# M168A.net
KiCad netlist of a schematic drawn in EAGLE
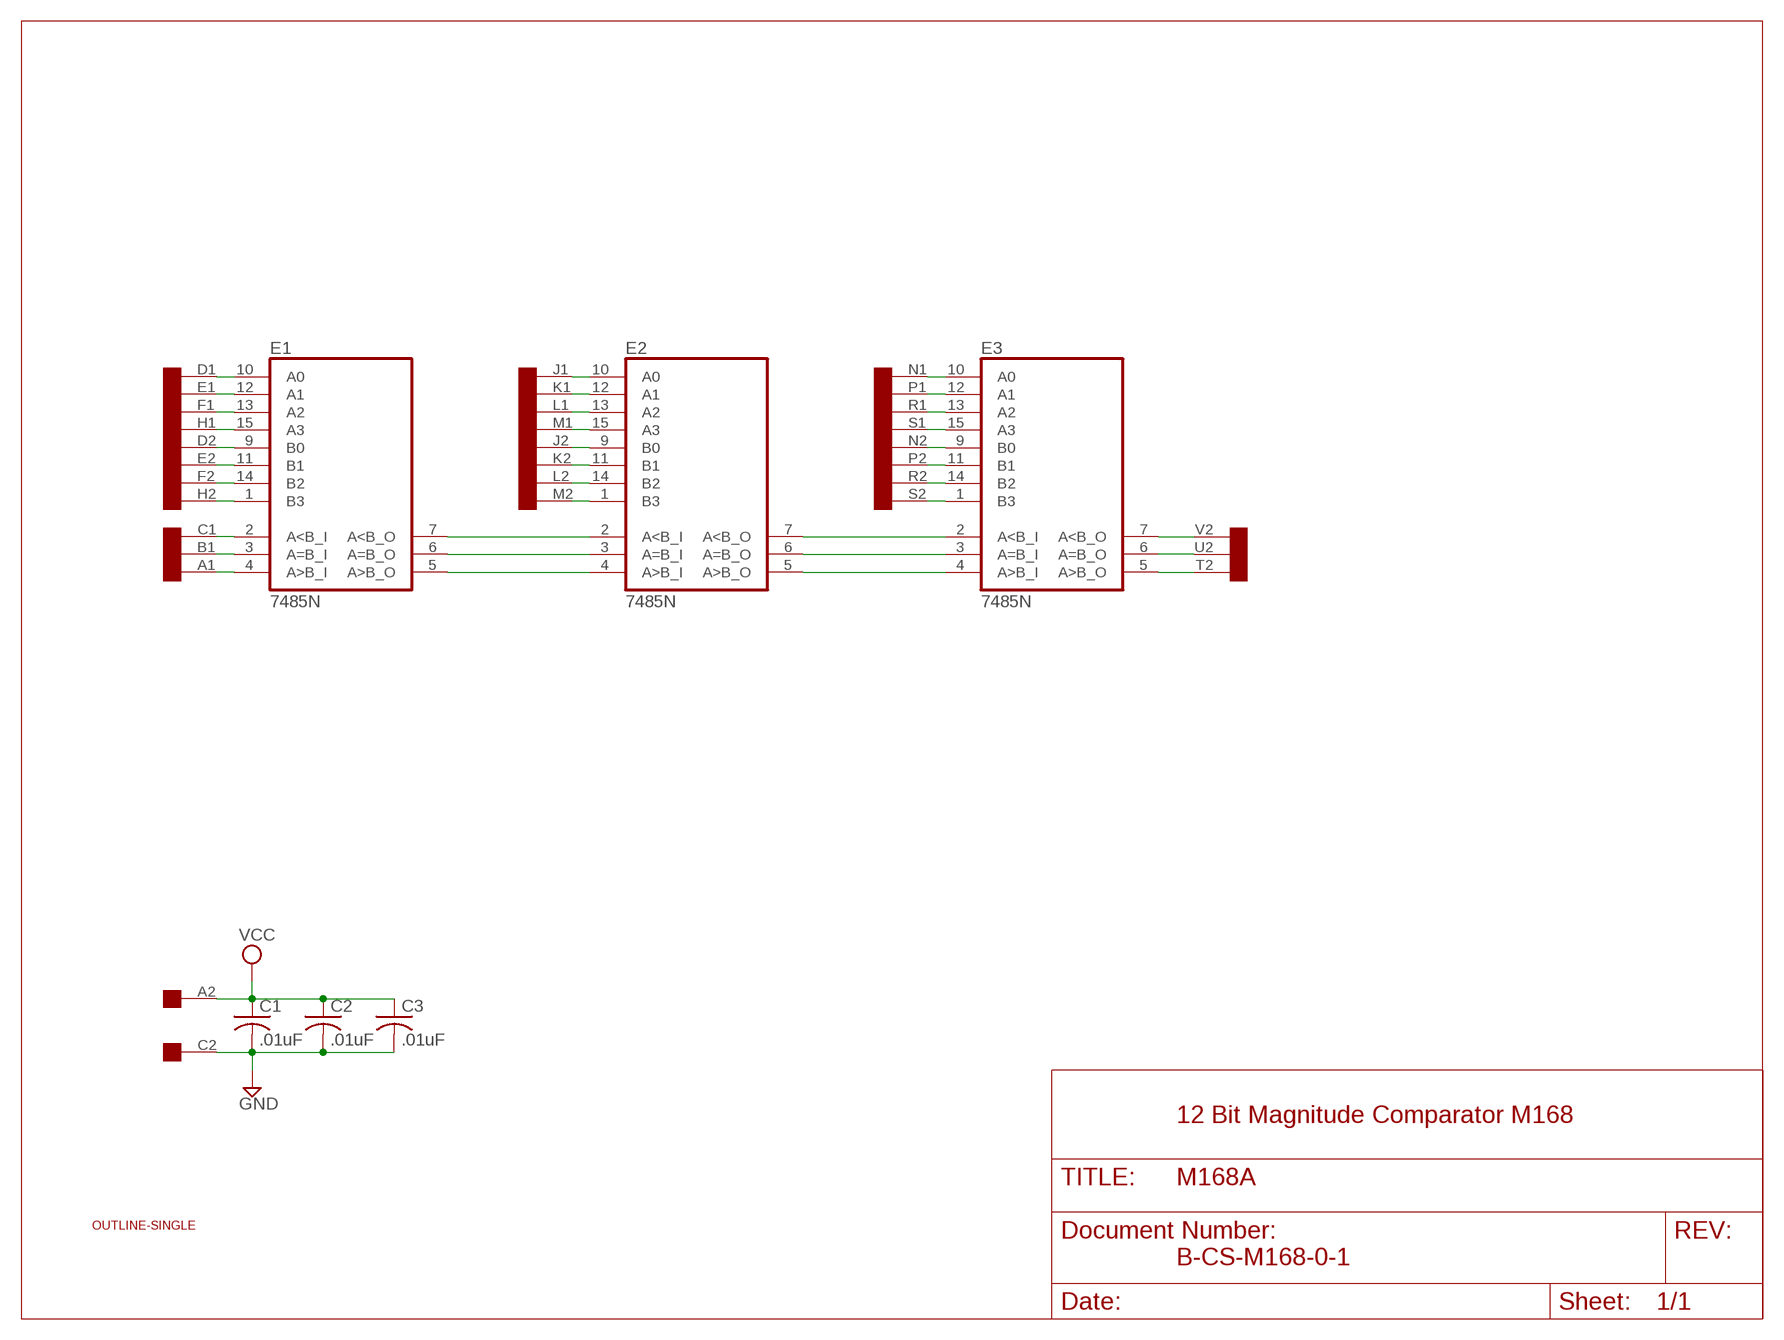
[diagram p0: schematic, sheet 1]

(export (version "E")
  (design (tool "Eeschema 10.0.6"))
  (components
    (comp (ref "C1")
      (value ".01uF")
      (footprint "eagle-import:C050-025X075")
      (libsource (lib "eagle-import") (part "C-US050-025X075"))
    )
    (comp (ref "C2")
      (value ".01uF")
      (footprint "eagle-import:C050-025X075")
      (libsource (lib "eagle-import") (part "C-US050-025X075"))
    )
    (comp (ref "C3")
      (value ".01uF")
      (footprint "eagle-import:C050-025X075")
      (libsource (lib "eagle-import") (part "C-US050-025X075"))
    )
    (comp (ref "E1")
      (value "7485N")
      (footprint "eagle-import:DIL16")
      (libsource (lib "eagle-import") (part "7485N"))
    )
    (comp (ref "E2")
      (value "7485N")
      (footprint "eagle-import:DIL16")
      (libsource (lib "eagle-import") (part "7485N"))
    )
    (comp (ref "E3")
      (value "7485N")
      (footprint "eagle-import:DIL16")
      (libsource (lib "eagle-import") (part "7485N"))
    )
    (comp (ref "U$1")
      (value "SINGLE")
      (footprint "eagle-import:EDGE-CON2")
      (libsource (lib "eagle-import") (part "SINGLE"))
    )
    (comp (ref "U$2")
      (value "OUTLINE-SINGLE")
      (footprint "eagle-import:SINGLE")
      (libsource (lib "eagle-import") (part "OUTLINE-SINGLE"))
    )
  )
  (nets
    (net (code "1") (name "GND") (class "Default")
      (node (ref "C1") (pin "2") (pinfunction "2_2") (pintype "passive"))
      (node (ref "C2") (pin "2") (pinfunction "2_2") (pintype "passive"))
      (node (ref "C3") (pin "2") (pinfunction "2_2") (pintype "passive"))
      (node (ref "U$1") (pin "C2") (pinfunction "1_C2") (pintype "bidirectional"))
    )
    (net (code "2") (name "Net-(E1A-A0)") (class "Default")
      (node (ref "E1") (pin "10") (pinfunction "A0_10") (pintype "input"))
      (node (ref "U$1") (pin "D1") (pinfunction "1_D1") (pintype "bidirectional"))
    )
    (net (code "3") (name "Net-(E1A-A1)") (class "Default")
      (node (ref "E1") (pin "12") (pinfunction "A1_12") (pintype "input"))
      (node (ref "U$1") (pin "E1") (pinfunction "1_E1") (pintype "bidirectional"))
    )
    (net (code "4") (name "Net-(E1A-A2)") (class "Default")
      (node (ref "E1") (pin "13") (pinfunction "A2_13") (pintype "input"))
      (node (ref "U$1") (pin "F1") (pinfunction "1_F1") (pintype "bidirectional"))
    )
    (net (code "5") (name "Net-(E1A-A3)") (class "Default")
      (node (ref "E1") (pin "15") (pinfunction "A3_15") (pintype "input"))
      (node (ref "U$1") (pin "H1") (pinfunction "1_H1") (pintype "bidirectional"))
    )
    (net (code "6") (name "Net-(E1A-A<B_I)") (class "Default")
      (node (ref "E1") (pin "2") (pinfunction "A<B_I_2") (pintype "input"))
      (node (ref "U$1") (pin "C1") (pinfunction "1_C1") (pintype "bidirectional"))
    )
    (net (code "7") (name "Net-(E1A-A<B_O)") (class "Default")
      (node (ref "E1") (pin "7") (pinfunction "A<B_O_7") (pintype "output"))
      (node (ref "E2") (pin "2") (pinfunction "A<B_I_2") (pintype "input"))
    )
    (net (code "8") (name "Net-(E1A-A=B_I)") (class "Default")
      (node (ref "E1") (pin "3") (pinfunction "A=B_I_3") (pintype "input"))
      (node (ref "U$1") (pin "B1") (pinfunction "1_B1") (pintype "bidirectional"))
    )
    (net (code "9") (name "Net-(E1A-A=B_O)") (class "Default")
      (node (ref "E1") (pin "6") (pinfunction "A=B_O_6") (pintype "output"))
      (node (ref "E2") (pin "3") (pinfunction "A=B_I_3") (pintype "input"))
    )
    (net (code "10") (name "Net-(E1A-A>B_I)") (class "Default")
      (node (ref "E1") (pin "4") (pinfunction "A>B_I_4") (pintype "input"))
      (node (ref "U$1") (pin "A1") (pinfunction "1_A1") (pintype "bidirectional"))
    )
    (net (code "11") (name "Net-(E1A-A>B_O)") (class "Default")
      (node (ref "E1") (pin "5") (pinfunction "A>B_O_5") (pintype "output"))
      (node (ref "E2") (pin "4") (pinfunction "A>B_I_4") (pintype "input"))
    )
    (net (code "12") (name "Net-(E1A-B0)") (class "Default")
      (node (ref "E1") (pin "9") (pinfunction "B0_9") (pintype "input"))
      (node (ref "U$1") (pin "D2") (pinfunction "1_D2") (pintype "bidirectional"))
    )
    (net (code "13") (name "Net-(E1A-B1)") (class "Default")
      (node (ref "E1") (pin "11") (pinfunction "B1_11") (pintype "input"))
      (node (ref "U$1") (pin "E2") (pinfunction "1_E2") (pintype "bidirectional"))
    )
    (net (code "14") (name "Net-(E1A-B2)") (class "Default")
      (node (ref "E1") (pin "14") (pinfunction "B2_14") (pintype "input"))
      (node (ref "U$1") (pin "F2") (pinfunction "1_F2") (pintype "bidirectional"))
    )
    (net (code "15") (name "Net-(E1A-B3)") (class "Default")
      (node (ref "E1") (pin "1") (pinfunction "B3_1") (pintype "input"))
      (node (ref "U$1") (pin "H2") (pinfunction "1_H2") (pintype "bidirectional"))
    )
    (net (code "16") (name "Net-(E2A-A0)") (class "Default")
      (node (ref "E2") (pin "10") (pinfunction "A0_10") (pintype "input"))
      (node (ref "U$1") (pin "J1") (pinfunction "1_J1") (pintype "bidirectional"))
    )
    (net (code "17") (name "Net-(E2A-A1)") (class "Default")
      (node (ref "E2") (pin "12") (pinfunction "A1_12") (pintype "input"))
      (node (ref "U$1") (pin "K1") (pinfunction "1_K1") (pintype "bidirectional"))
    )
    (net (code "18") (name "Net-(E2A-A2)") (class "Default")
      (node (ref "E2") (pin "13") (pinfunction "A2_13") (pintype "input"))
      (node (ref "U$1") (pin "L1") (pinfunction "1_L1") (pintype "bidirectional"))
    )
    (net (code "19") (name "Net-(E2A-A3)") (class "Default")
      (node (ref "E2") (pin "15") (pinfunction "A3_15") (pintype "input"))
      (node (ref "U$1") (pin "M1") (pinfunction "1_M1") (pintype "bidirectional"))
    )
    (net (code "20") (name "Net-(E2A-A<B_O)") (class "Default")
      (node (ref "E2") (pin "7") (pinfunction "A<B_O_7") (pintype "output"))
      (node (ref "E3") (pin "2") (pinfunction "A<B_I_2") (pintype "input"))
    )
    (net (code "21") (name "Net-(E2A-A=B_O)") (class "Default")
      (node (ref "E2") (pin "6") (pinfunction "A=B_O_6") (pintype "output"))
      (node (ref "E3") (pin "3") (pinfunction "A=B_I_3") (pintype "input"))
    )
    (net (code "22") (name "Net-(E2A-A>B_O)") (class "Default")
      (node (ref "E2") (pin "5") (pinfunction "A>B_O_5") (pintype "output"))
      (node (ref "E3") (pin "4") (pinfunction "A>B_I_4") (pintype "input"))
    )
    (net (code "23") (name "Net-(E2A-B0)") (class "Default")
      (node (ref "E2") (pin "9") (pinfunction "B0_9") (pintype "input"))
      (node (ref "U$1") (pin "J2") (pinfunction "1_J2") (pintype "bidirectional"))
    )
    (net (code "24") (name "Net-(E2A-B1)") (class "Default")
      (node (ref "E2") (pin "11") (pinfunction "B1_11") (pintype "input"))
      (node (ref "U$1") (pin "K2") (pinfunction "1_K2") (pintype "bidirectional"))
    )
    (net (code "25") (name "Net-(E2A-B2)") (class "Default")
      (node (ref "E2") (pin "14") (pinfunction "B2_14") (pintype "input"))
      (node (ref "U$1") (pin "L2") (pinfunction "1_L2") (pintype "bidirectional"))
    )
    (net (code "26") (name "Net-(E2A-B3)") (class "Default")
      (node (ref "E2") (pin "1") (pinfunction "B3_1") (pintype "input"))
      (node (ref "U$1") (pin "M2") (pinfunction "1_M2") (pintype "bidirectional"))
    )
    (net (code "27") (name "Net-(E3A-A0)") (class "Default")
      (node (ref "E3") (pin "10") (pinfunction "A0_10") (pintype "input"))
      (node (ref "U$1") (pin "N1") (pinfunction "1_N1") (pintype "bidirectional"))
    )
    (net (code "28") (name "Net-(E3A-A1)") (class "Default")
      (node (ref "E3") (pin "12") (pinfunction "A1_12") (pintype "input"))
      (node (ref "U$1") (pin "P1") (pinfunction "1_P1") (pintype "bidirectional"))
    )
    (net (code "29") (name "Net-(E3A-A2)") (class "Default")
      (node (ref "E3") (pin "13") (pinfunction "A2_13") (pintype "input"))
      (node (ref "U$1") (pin "R1") (pinfunction "1_R1") (pintype "bidirectional"))
    )
    (net (code "30") (name "Net-(E3A-A3)") (class "Default")
      (node (ref "E3") (pin "15") (pinfunction "A3_15") (pintype "input"))
      (node (ref "U$1") (pin "S1") (pinfunction "1_S1") (pintype "bidirectional"))
    )
    (net (code "31") (name "Net-(E3A-A<B_O)") (class "Default")
      (node (ref "E3") (pin "7") (pinfunction "A<B_O_7") (pintype "output"))
      (node (ref "U$1") (pin "V2") (pinfunction "1_V2") (pintype "bidirectional"))
    )
    (net (code "32") (name "Net-(E3A-A=B_O)") (class "Default")
      (node (ref "E3") (pin "6") (pinfunction "A=B_O_6") (pintype "output"))
      (node (ref "U$1") (pin "U2") (pinfunction "1_U2") (pintype "bidirectional"))
    )
    (net (code "33") (name "Net-(E3A-A>B_O)") (class "Default")
      (node (ref "E3") (pin "5") (pinfunction "A>B_O_5") (pintype "output"))
      (node (ref "U$1") (pin "T2") (pinfunction "1_T2") (pintype "bidirectional"))
    )
    (net (code "34") (name "Net-(E3A-B0)") (class "Default")
      (node (ref "E3") (pin "9") (pinfunction "B0_9") (pintype "input"))
      (node (ref "U$1") (pin "N2") (pinfunction "1_N2") (pintype "bidirectional"))
    )
    (net (code "35") (name "Net-(E3A-B1)") (class "Default")
      (node (ref "E3") (pin "11") (pinfunction "B1_11") (pintype "input"))
      (node (ref "U$1") (pin "P2") (pinfunction "1_P2") (pintype "bidirectional"))
    )
    (net (code "36") (name "Net-(E3A-B2)") (class "Default")
      (node (ref "E3") (pin "14") (pinfunction "B2_14") (pintype "input"))
      (node (ref "U$1") (pin "R2") (pinfunction "1_R2") (pintype "bidirectional"))
    )
    (net (code "37") (name "Net-(E3A-B3)") (class "Default")
      (node (ref "E3") (pin "1") (pinfunction "B3_1") (pintype "input"))
      (node (ref "U$1") (pin "S2") (pinfunction "1_S2") (pintype "bidirectional"))
    )
    (net (code "38") (name "VCC") (class "Default")
      (node (ref "C1") (pin "1") (pinfunction "1_1") (pintype "passive"))
      (node (ref "C2") (pin "1") (pinfunction "1_1") (pintype "passive"))
      (node (ref "C3") (pin "1") (pinfunction "1_1") (pintype "passive"))
      (node (ref "U$1") (pin "A2") (pinfunction "1_A2") (pintype "bidirectional"))
    )
  )
)
